# MotorDriver.net
KiCad netlist of a schematic drawn in EAGLE
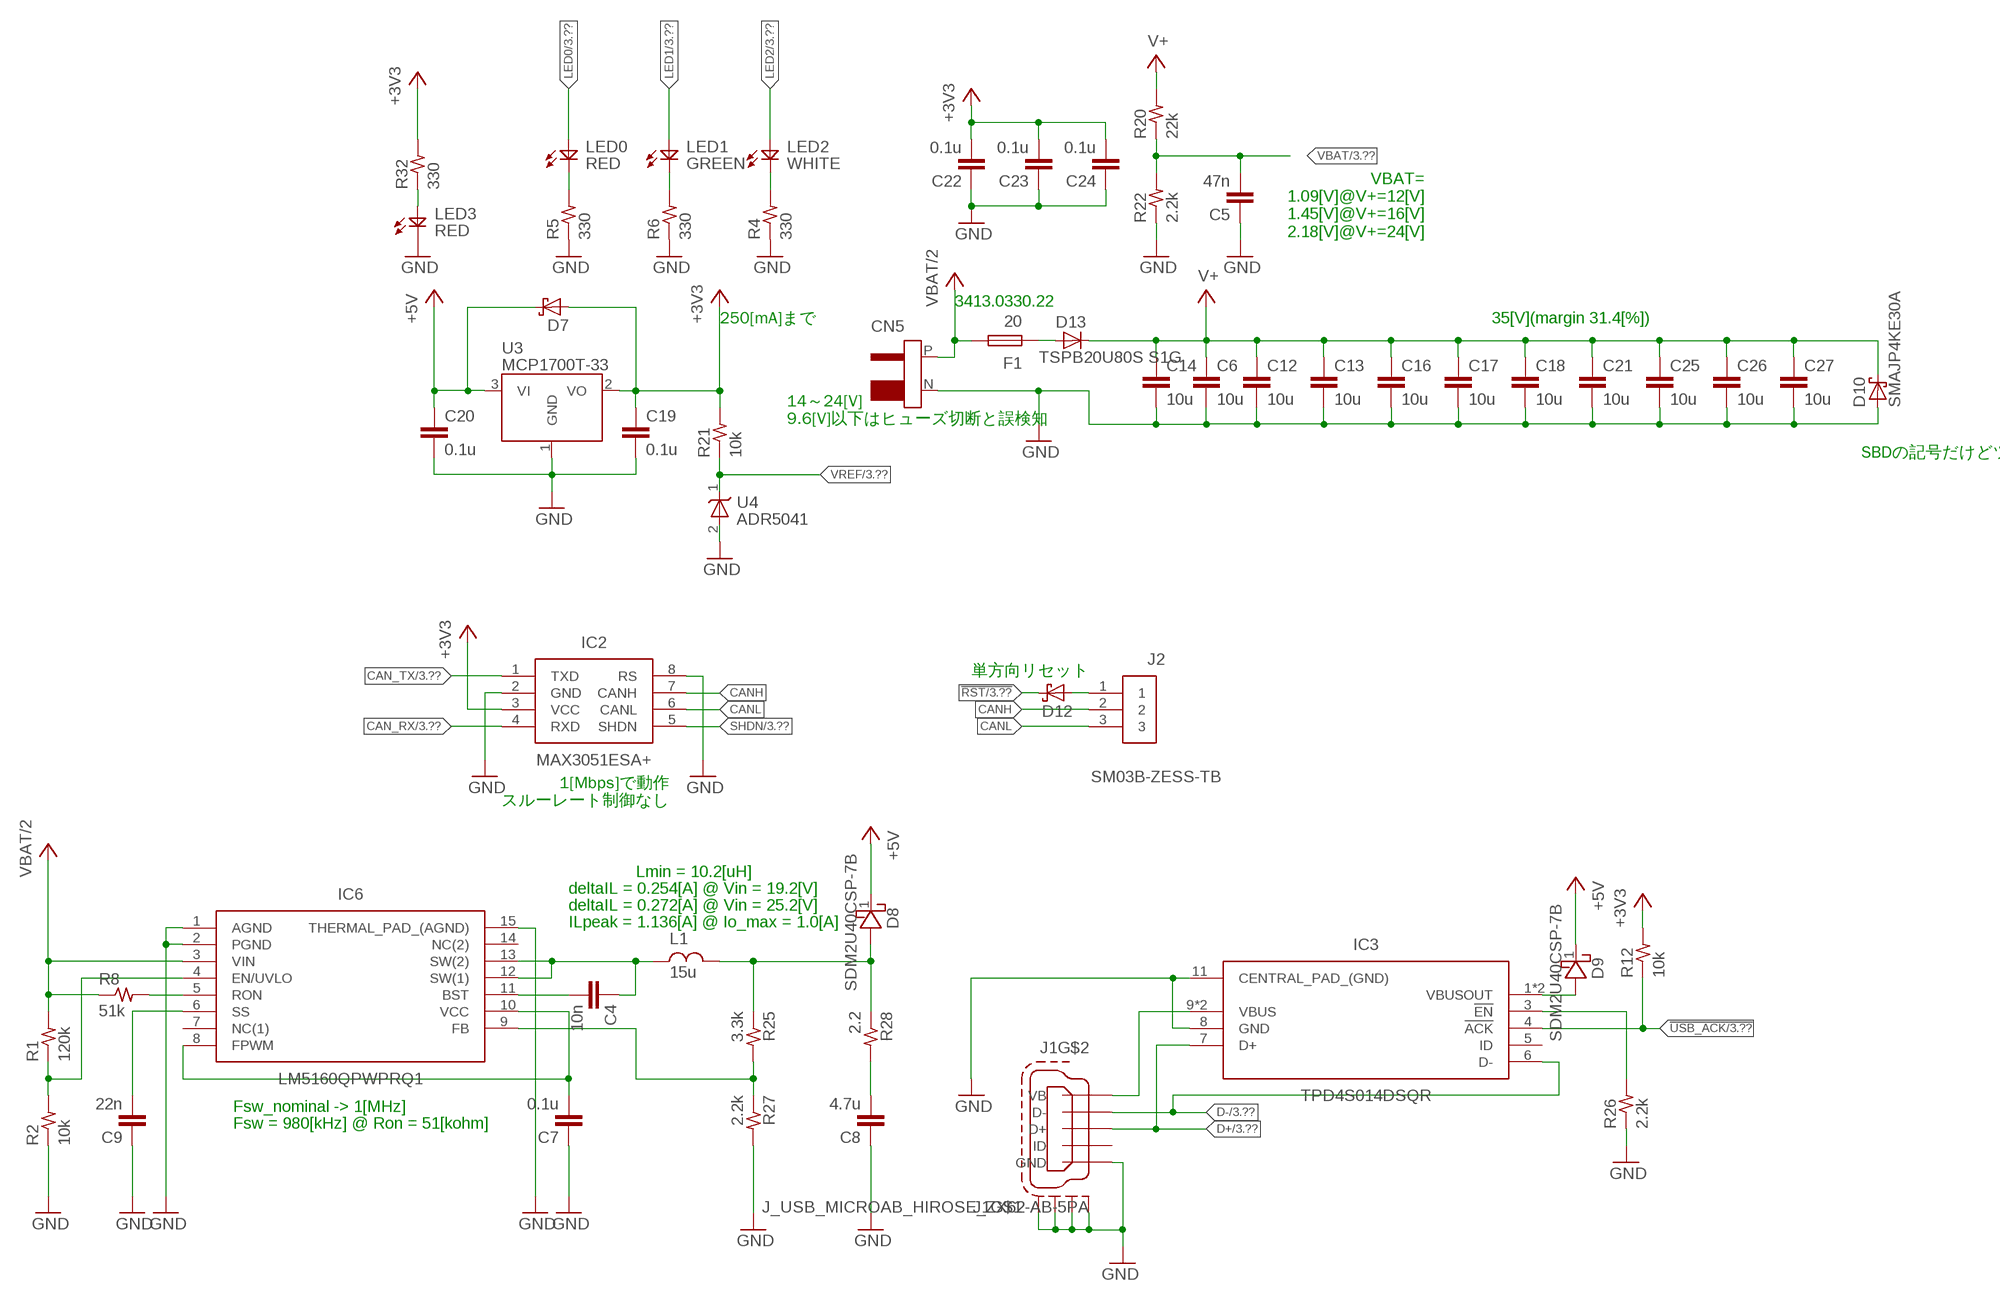
[diagram p0: schematic, sheet 1]
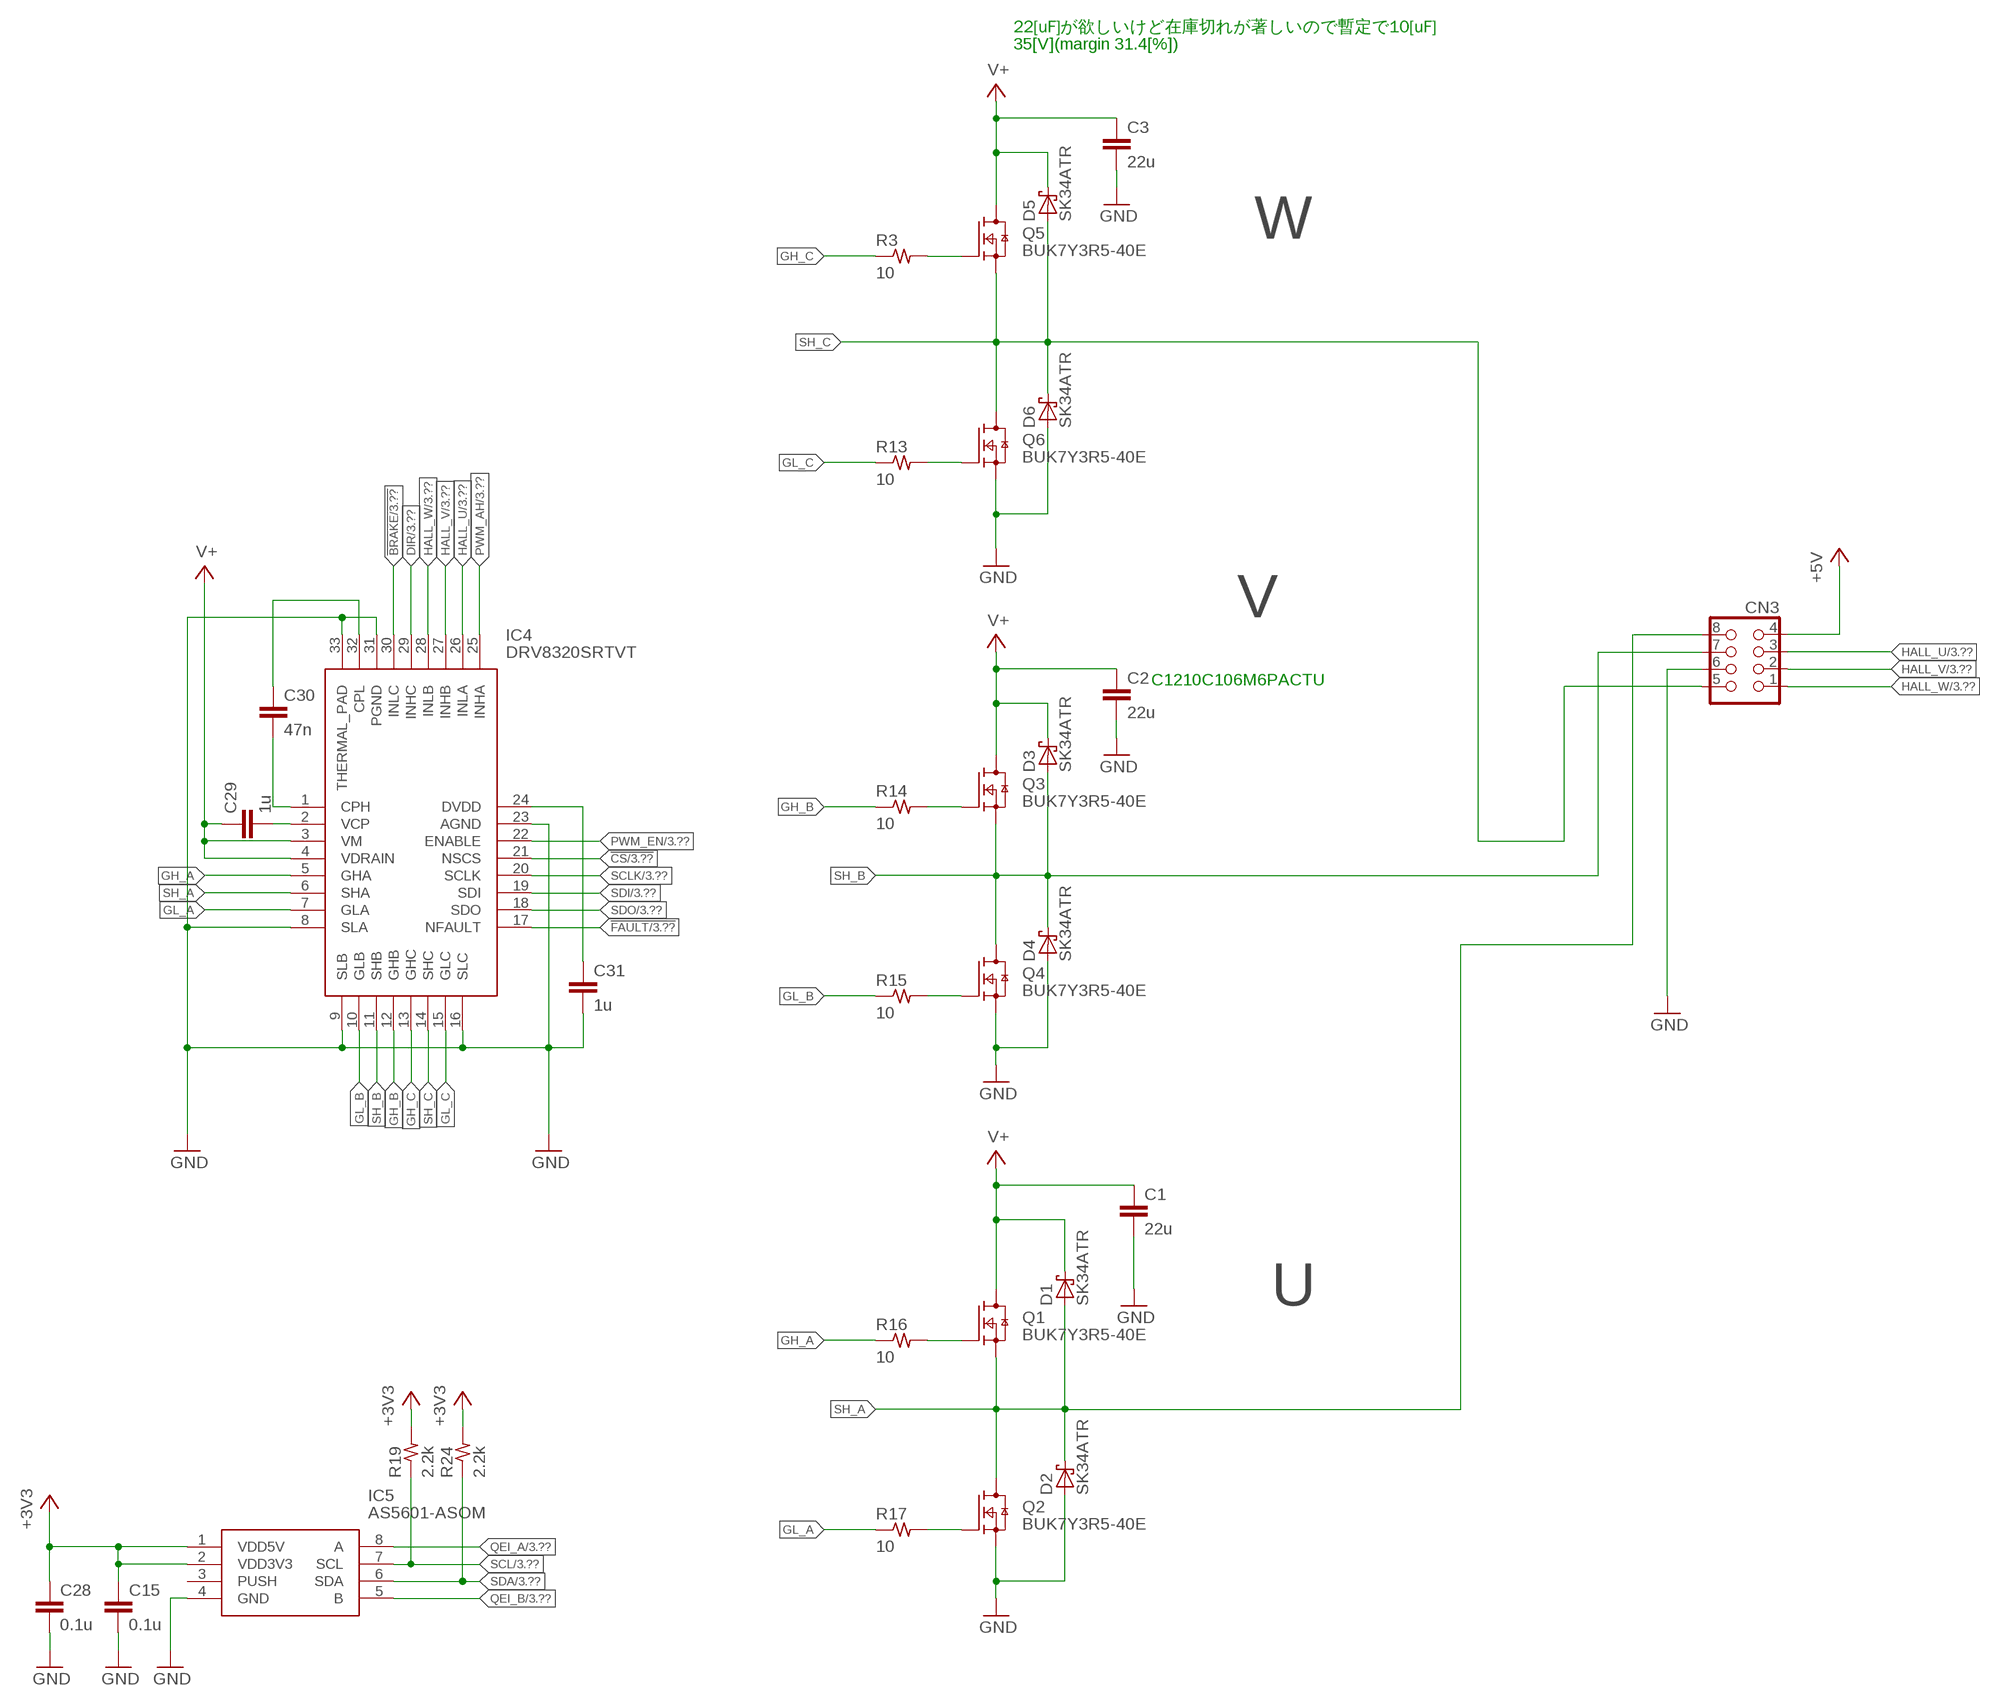
[diagram p1: schematic, sheet 2]
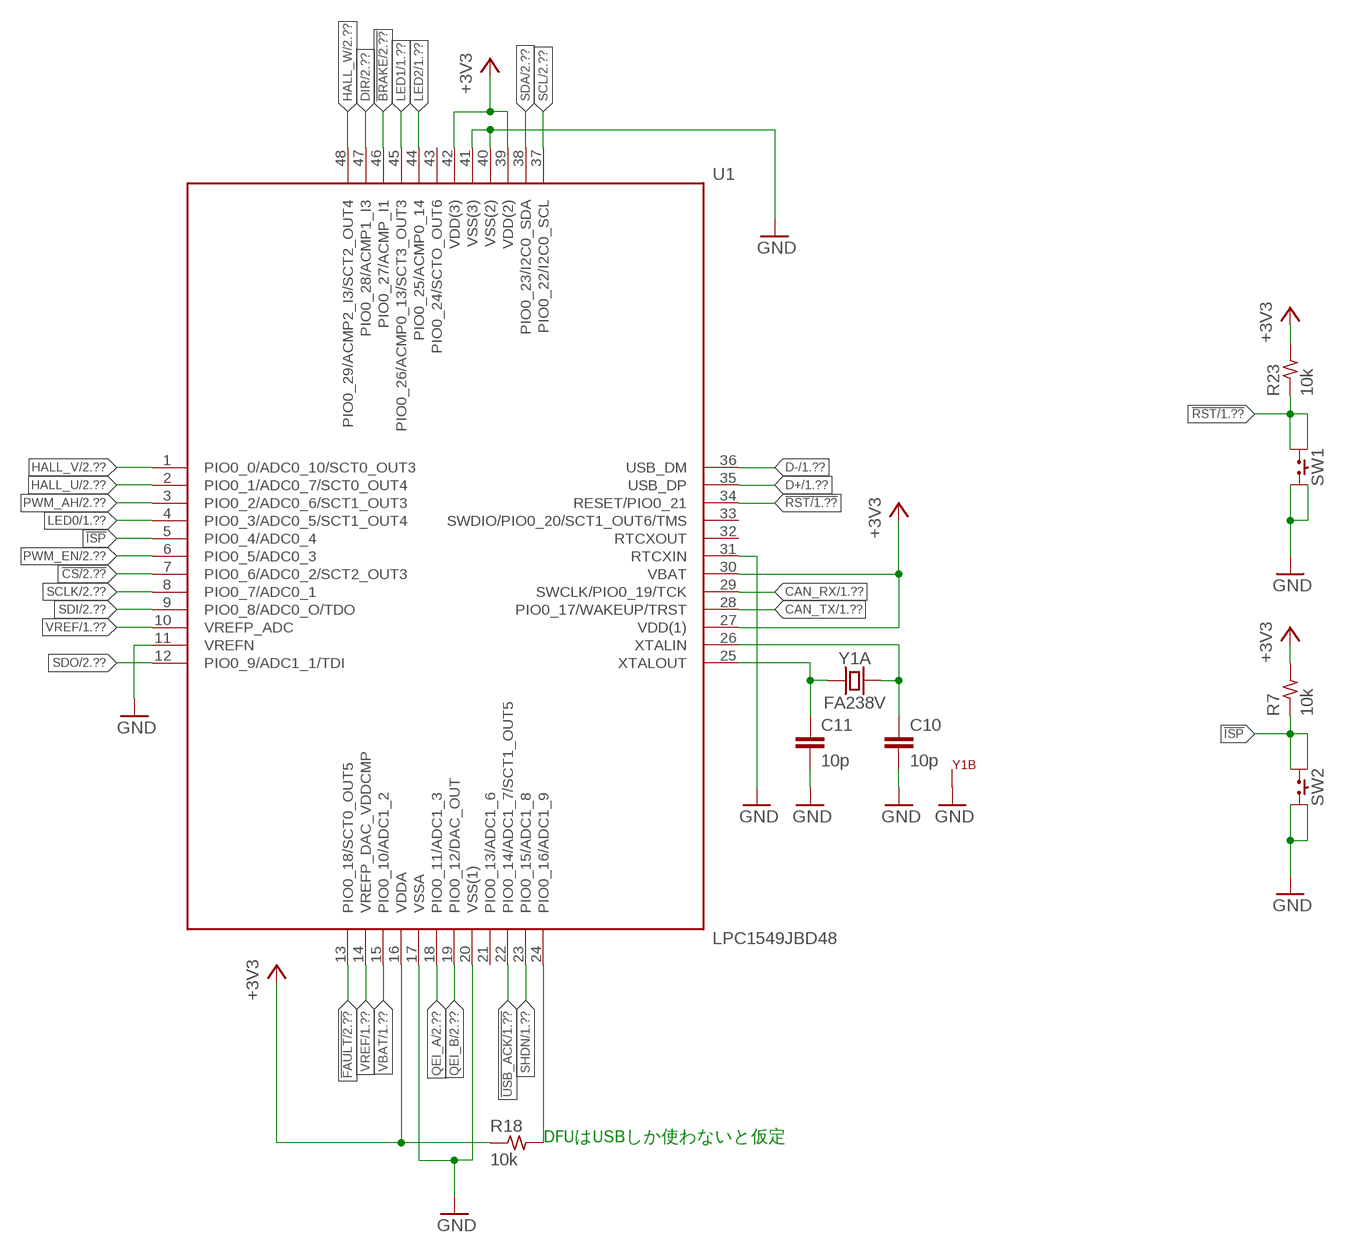
[diagram p2: schematic, sheet 3]

(export (version "E")
  (design (tool "Eeschema 10.0.6"))
  (components
    (comp (ref "C10")
      (value "10p")
      (footprint "eagle-import:C1005")
      (libsource (lib "eagle-import") (part "C1005"))
    )
    (comp (ref "C11")
      (value "10p")
      (footprint "eagle-import:C1005")
      (libsource (lib "eagle-import") (part "C1005"))
    )
    (comp (ref "R7")
      (value "10k")
      (footprint "eagle-import:R1005")
      (libsource (lib "eagle-import") (part "R1005"))
    )
    (comp (ref "R18")
      (value "10k")
      (footprint "eagle-import:R1005")
      (libsource (lib "eagle-import") (part "R1005"))
    )
    (comp (ref "R23")
      (value "10k")
      (footprint "eagle-import:R1005")
      (libsource (lib "eagle-import") (part "R1005"))
    )
    (comp (ref "SW1")
      (value "SKRP")
      (footprint "eagle-import:SKRP")
      (libsource (lib "eagle-import") (part "SKRP"))
    )
    (comp (ref "SW2")
      (value "SKRP")
      (footprint "eagle-import:SKRP")
      (libsource (lib "eagle-import") (part "SKRP"))
    )
    (comp (ref "U1")
      (value "LPC1549JBD48")
      (footprint "eagle-import:QFP48")
      (libsource (lib "eagle-import") (part "LPC1549JBD48"))
    )
    (comp (ref "Y1")
      (value "FA238V")
      (footprint "eagle-import:EPSON_FA238V")
      (libsource (lib "eagle-import") (part "FA238V"))
    )
    (comp (ref "C4")
      (value "10n")
      (footprint "eagle-import:C1005")
      (libsource (lib "eagle-import") (part "C1005"))
    )
    (comp (ref "C5")
      (value "47n")
      (footprint "eagle-import:C1005")
      (libsource (lib "eagle-import") (part "C1005"))
    )
    (comp (ref "C6")
      (value "10u")
      (footprint "eagle-import:C3225")
      (libsource (lib "eagle-import") (part "C3225"))
    )
    (comp (ref "C7")
      (value "0.1u")
      (footprint "eagle-import:C1005")
      (libsource (lib "eagle-import") (part "C1005"))
    )
    (comp (ref "C8")
      (value "4.7u")
      (footprint "eagle-import:1608")
      (libsource (lib "eagle-import") (part "Passive_1073310_C1608"))
    )
    (comp (ref "C9")
      (value "22n")
      (footprint "eagle-import:C1005")
      (libsource (lib "eagle-import") (part "C1005"))
    )
    (comp (ref "C12")
      (value "10u")
      (footprint "eagle-import:C3225")
      (libsource (lib "eagle-import") (part "C3225"))
    )
    (comp (ref "C13")
      (value "10u")
      (footprint "eagle-import:C3225")
      (libsource (lib "eagle-import") (part "C3225"))
    )
    (comp (ref "C14")
      (value "10u")
      (footprint "eagle-import:C3225")
      (libsource (lib "eagle-import") (part "C3225"))
    )
    (comp (ref "C16")
      (value "10u")
      (footprint "eagle-import:C3225")
      (libsource (lib "eagle-import") (part "C3225"))
    )
    (comp (ref "C17")
      (value "10u")
      (footprint "eagle-import:C3225")
      (libsource (lib "eagle-import") (part "C3225"))
    )
    (comp (ref "C18")
      (value "10u")
      (footprint "eagle-import:C3225")
      (libsource (lib "eagle-import") (part "C3225"))
    )
    (comp (ref "C19")
      (value "0.1u")
      (footprint "eagle-import:C1005")
      (libsource (lib "eagle-import") (part "C1005"))
    )
    (comp (ref "C20")
      (value "0.1u")
      (footprint "eagle-import:C1005")
      (libsource (lib "eagle-import") (part "C1005"))
    )
    (comp (ref "C21")
      (value "10u")
      (footprint "eagle-import:C3225")
      (libsource (lib "eagle-import") (part "C3225"))
    )
    (comp (ref "C22")
      (value "0.1u")
      (footprint "eagle-import:C1005")
      (libsource (lib "eagle-import") (part "C1005"))
    )
    (comp (ref "C23")
      (value "0.1u")
      (footprint "eagle-import:C1005")
      (libsource (lib "eagle-import") (part "C1005"))
    )
    (comp (ref "C24")
      (value "0.1u")
      (footprint "eagle-import:C1005")
      (libsource (lib "eagle-import") (part "C1005"))
    )
    (comp (ref "C25")
      (value "10u")
      (footprint "eagle-import:C3225")
      (libsource (lib "eagle-import") (part "C3225"))
    )
    (comp (ref "C26")
      (value "10u")
      (footprint "eagle-import:C3225")
      (libsource (lib "eagle-import") (part "C3225"))
    )
    (comp (ref "C27")
      (value "10u")
      (footprint "eagle-import:C3225")
      (libsource (lib "eagle-import") (part "C3225"))
    )
    (comp (ref "CN5")
      (value "T-CON")
      (footprint "eagle-import:T-CON")
      (libsource (lib "eagle-import") (part "T-CON"))
    )
    (comp (ref "D7")
      (value "SBD-SOD523")
      (footprint "eagle-import:DIODE_SOD523")
      (libsource (lib "eagle-import") (part "SBD-SOD523"))
    )
    (comp (ref "D8")
      (value "SDM2U40CSP-7B")
      (footprint "eagle-import:X3-WLB1608-2")
      (libsource (lib "eagle-import") (part "SDM2U40CSP-7B"))
    )
    (comp (ref "D9")
      (value "SDM2U40CSP-7B")
      (footprint "eagle-import:X3-WLB1608-2")
      (libsource (lib "eagle-import") (part "SDM2U40CSP-7B"))
    )
    (comp (ref "D10")
      (value "SMAJP4KE30A")
      (footprint "eagle-import:DO-214AC")
      (libsource (lib "eagle-import") (part "SBD-DO-214AC"))
    )
    (comp (ref "D12")
      (value "SBD-SOD523")
      (footprint "eagle-import:DIODE_SOD523")
      (libsource (lib "eagle-import") (part "SBD-SOD523"))
    )
    (comp (ref "D13")
      (value "TSPB20U80S S1G")
      (footprint "eagle-import:SMPC")
      (libsource (lib "eagle-import") (part "DIODE-SMPC"))
    )
    (comp (ref "F1")
      (value "20")
      (footprint "eagle-import:3216")
      (libsource (lib "eagle-import") (part "F3216"))
    )
    (comp (ref "IC2")
      (value "MAX3051ESA+")
      (footprint "eagle-import:SOIC127P600X175-8N")
      (fields (field (name "RS_PART_NUMBER") "7329005"))
      (libsource (lib "eagle-import") (part "MAX3051ESA+"))
    )
    (comp (ref "IC3")
      (value "TPD4S014DSQR")
      (footprint "eagle-import:SON40P200X200X80-11N")
      (fields (field (name "RS_PART_NUMBER") "7422968"))
      (libsource (lib "eagle-import") (part "TPD4S014DSQR"))
    )
    (comp (ref "IC6")
      (value "LM5160QPWPRQ1")
      (footprint "eagle-import:SOP65P640X110-15N")
      (libsource (lib "eagle-import") (part "LM5160QPWPRQ1"))
    )
    (comp (ref "J1")
      (value "J_USB_MICROAB_HIROSE_ZX62-AB-5PA")
      (footprint "eagle-import:J_USB_MICROAB_HIROSE_ZX62-AB-5PA")
      (libsource (lib "eagle-import") (part "J_USB_MICROAB_HIROSE_ZX62-AB-5PA"))
    )
    (comp (ref "J2")
      (value "SM03B-ZESS-TB")
      (footprint "eagle-import:SM03B-ZESS-TB")
      (libsource (lib "eagle-import") (part "SM03B-ZESS-TB"))
    )
    (comp (ref "L1")
      (value "15u")
      (footprint "eagle-import:L4949")
      (libsource (lib "eagle-import") (part "L50"))
    )
    (comp (ref "LED0")
      (value "RED")
      (footprint "eagle-import:LED1608")
      (libsource (lib "eagle-import") (part "LED1608"))
    )
    (comp (ref "LED1")
      (value "GREEN")
      (footprint "eagle-import:LED1608")
      (libsource (lib "eagle-import") (part "LED1608"))
    )
    (comp (ref "LED2")
      (value "WHITE")
      (footprint "eagle-import:LED1608")
      (libsource (lib "eagle-import") (part "LED1608"))
    )
    (comp (ref "LED3")
      (value "RED")
      (footprint "eagle-import:LED1608")
      (libsource (lib "eagle-import") (part "LED1608"))
    )
    (comp (ref "R1")
      (value "120k")
      (footprint "eagle-import:R1005")
      (libsource (lib "eagle-import") (part "R1005"))
    )
    (comp (ref "R2")
      (value "10k")
      (footprint "eagle-import:R1005")
      (libsource (lib "eagle-import") (part "R1005"))
    )
    (comp (ref "R4")
      (value "330")
      (footprint "eagle-import:R1005")
      (libsource (lib "eagle-import") (part "R1005"))
    )
    (comp (ref "R5")
      (value "330")
      (footprint "eagle-import:R1005")
      (libsource (lib "eagle-import") (part "R1005"))
    )
    (comp (ref "R6")
      (value "330")
      (footprint "eagle-import:R1005")
      (libsource (lib "eagle-import") (part "R1005"))
    )
    (comp (ref "R8")
      (value "51k")
      (footprint "eagle-import:R1005")
      (libsource (lib "eagle-import") (part "R1005"))
    )
    (comp (ref "R12")
      (value "10k")
      (footprint "eagle-import:R1005")
      (libsource (lib "eagle-import") (part "R1005"))
    )
    (comp (ref "R20")
      (value "22k")
      (footprint "eagle-import:R1005")
      (libsource (lib "eagle-import") (part "R1005"))
    )
    (comp (ref "R21")
      (value "10k")
      (footprint "eagle-import:R1005")
      (libsource (lib "eagle-import") (part "R1005"))
    )
    (comp (ref "R22")
      (value "2.2k")
      (footprint "eagle-import:R1005")
      (libsource (lib "eagle-import") (part "R1005"))
    )
    (comp (ref "R25")
      (value "3.3k")
      (footprint "eagle-import:R1005")
      (libsource (lib "eagle-import") (part "R1005"))
    )
    (comp (ref "R26")
      (value "2.2k")
      (footprint "eagle-import:R1005")
      (libsource (lib "eagle-import") (part "R1005"))
    )
    (comp (ref "R27")
      (value "2.2k")
      (footprint "eagle-import:R1005")
      (libsource (lib "eagle-import") (part "R1005"))
    )
    (comp (ref "R28")
      (value "2.2")
      (footprint "eagle-import:R1005")
      (libsource (lib "eagle-import") (part "R1005"))
    )
    (comp (ref "R32")
      (value "330")
      (footprint "eagle-import:R1005")
      (libsource (lib "eagle-import") (part "R1005"))
    )
    (comp (ref "U3")
      (value "MCP1700T-33")
      (footprint "eagle-import:SOT23-3")
      (libsource (lib "eagle-import") (part "MCP1700T-33"))
    )
    (comp (ref "U4")
      (value "ADR5041")
      (footprint "eagle-import:SC70-3")
      (libsource (lib "eagle-import") (part "ADR5041"))
    )
    (comp (ref "C1")
      (value "22u")
      (footprint "eagle-import:C3225")
      (libsource (lib "eagle-import") (part "C3225"))
    )
    (comp (ref "C2")
      (value "22u")
      (footprint "eagle-import:C3225")
      (libsource (lib "eagle-import") (part "C3225"))
    )
    (comp (ref "C3")
      (value "22u")
      (footprint "eagle-import:C3225")
      (libsource (lib "eagle-import") (part "C3225"))
    )
    (comp (ref "C15")
      (value "0.1u")
      (footprint "eagle-import:C1005")
      (libsource (lib "eagle-import") (part "C1005"))
    )
    (comp (ref "C28")
      (value "0.1u")
      (footprint "eagle-import:C1005")
      (libsource (lib "eagle-import") (part "C1005"))
    )
    (comp (ref "C29")
      (value "1u")
      (footprint "eagle-import:C1005")
      (libsource (lib "eagle-import") (part "C1005"))
    )
    (comp (ref "C30")
      (value "47n")
      (footprint "eagle-import:C1005")
      (libsource (lib "eagle-import") (part "C1005"))
    )
    (comp (ref "C31")
      (value "1u")
      (footprint "eagle-import:C1005")
      (libsource (lib "eagle-import") (part "C1005"))
    )
    (comp (ref "CN3")
      (value "43045-0800")
      (footprint "eagle-import:43045-0800")
      (libsource (lib "eagle-import") (part "43045-0800"))
    )
    (comp (ref "D1")
      (value "SK34ATR")
      (footprint "eagle-import:DO-214AC")
      (libsource (lib "eagle-import") (part "SBD-DO-214AC"))
    )
    (comp (ref "D2")
      (value "SK34ATR")
      (footprint "eagle-import:DO-214AC")
      (libsource (lib "eagle-import") (part "SBD-DO-214AC"))
    )
    (comp (ref "D3")
      (value "SK34ATR")
      (footprint "eagle-import:DO-214AC")
      (libsource (lib "eagle-import") (part "SBD-DO-214AC"))
    )
    (comp (ref "D4")
      (value "SK34ATR")
      (footprint "eagle-import:DO-214AC")
      (libsource (lib "eagle-import") (part "SBD-DO-214AC"))
    )
    (comp (ref "D5")
      (value "SK34ATR")
      (footprint "eagle-import:DO-214AC")
      (libsource (lib "eagle-import") (part "SBD-DO-214AC"))
    )
    (comp (ref "D6")
      (value "SK34ATR")
      (footprint "eagle-import:DO-214AC")
      (libsource (lib "eagle-import") (part "SBD-DO-214AC"))
    )
    (comp (ref "IC4")
      (value "DRV8320SRTVT")
      (footprint "eagle-import:QFN50P500X500X80-33N")
      (libsource (lib "eagle-import") (part "DRV8320SRTVT"))
    )
    (comp (ref "IC5")
      (value "AS5601-ASOM")
      (footprint "eagle-import:SOIC127P600X175-8N")
      (fields (field (name "RS_PART_NUMBER") "1700757"))
      (libsource (lib "eagle-import") (part "AS5601-ASOM"))
    )
    (comp (ref "Q1")
      (value "BUK7Y3R5-40E")
      (footprint "eagle-import:SOT669")
      (libsource (lib "eagle-import") (part "BUK7Y3R5-40E"))
    )
    (comp (ref "Q2")
      (value "BUK7Y3R5-40E")
      (footprint "eagle-import:SOT669")
      (libsource (lib "eagle-import") (part "BUK7Y3R5-40E"))
    )
    (comp (ref "Q3")
      (value "BUK7Y3R5-40E")
      (footprint "eagle-import:SOT669")
      (libsource (lib "eagle-import") (part "BUK7Y3R5-40E"))
    )
    (comp (ref "Q4")
      (value "BUK7Y3R5-40E")
      (footprint "eagle-import:SOT669")
      (libsource (lib "eagle-import") (part "BUK7Y3R5-40E"))
    )
    (comp (ref "Q5")
      (value "BUK7Y3R5-40E")
      (footprint "eagle-import:SOT669")
      (libsource (lib "eagle-import") (part "BUK7Y3R5-40E"))
    )
    (comp (ref "Q6")
      (value "BUK7Y3R5-40E")
      (footprint "eagle-import:SOT669")
      (libsource (lib "eagle-import") (part "BUK7Y3R5-40E"))
    )
    (comp (ref "R3")
      (value "10")
      (footprint "eagle-import:R1608")
      (libsource (lib "eagle-import") (part "R1608"))
    )
    (comp (ref "R13")
      (value "10")
      (footprint "eagle-import:R1608")
      (libsource (lib "eagle-import") (part "R1608"))
    )
    (comp (ref "R14")
      (value "10")
      (footprint "eagle-import:R1608")
      (libsource (lib "eagle-import") (part "R1608"))
    )
    (comp (ref "R15")
      (value "10")
      (footprint "eagle-import:R1608")
      (libsource (lib "eagle-import") (part "R1608"))
    )
    (comp (ref "R16")
      (value "10")
      (footprint "eagle-import:R1608")
      (libsource (lib "eagle-import") (part "R1608"))
    )
    (comp (ref "R17")
      (value "10")
      (footprint "eagle-import:R1608")
      (libsource (lib "eagle-import") (part "R1608"))
    )
    (comp (ref "R19")
      (value "2.2k")
      (footprint "eagle-import:R1005")
      (libsource (lib "eagle-import") (part "R1005"))
    )
    (comp (ref "R24")
      (value "2.2k")
      (footprint "eagle-import:R1005")
      (libsource (lib "eagle-import") (part "R1005"))
    )
  )
  (nets
    (net (code "1") (name "+3V3") (class "Default")
      (node (ref "C15") (pin "1") (pinfunction "1_1") (pintype "passive"))
      (node (ref "C19") (pin "1") (pinfunction "1_1") (pintype "passive"))
      (node (ref "C22") (pin "2") (pinfunction "2_2") (pintype "passive"))
      (node (ref "C23") (pin "2") (pinfunction "2_2") (pintype "passive"))
      (node (ref "C24") (pin "2") (pinfunction "2_2") (pintype "passive"))
      (node (ref "C28") (pin "1") (pinfunction "1_1") (pintype "passive"))
      (node (ref "D7") (pin "A") (pinfunction "A_A") (pintype "passive"))
      (node (ref "IC2") (pin "3") (pinfunction "VCC_3") (pintype "power_in"))
      (node (ref "IC5") (pin "1") (pinfunction "VDD5V_1") (pintype "power_in"))
      (node (ref "IC5") (pin "2") (pinfunction "VDD3V3_2") (pintype "power_in"))
      (node (ref "R12") (pin "2") (pinfunction "2_2") (pintype "passive"))
      (node (ref "R18") (pin "1") (pinfunction "1_1") (pintype "passive"))
      (node (ref "R19") (pin "2") (pinfunction "2_2") (pintype "passive"))
      (node (ref "R21") (pin "2") (pinfunction "2_2") (pintype "passive"))
      (node (ref "R23") (pin "2") (pinfunction "2_2") (pintype "passive"))
      (node (ref "R24") (pin "2") (pinfunction "2_2") (pintype "passive"))
      (node (ref "R32") (pin "2") (pinfunction "2_2") (pintype "passive"))
      (node (ref "R7") (pin "2") (pinfunction "2_2") (pintype "passive"))
      (node (ref "U1") (pin "16") (pinfunction "VDDA_16") (pintype "passive"))
      (node (ref "U1") (pin "27") (pinfunction "VDD(1)_27") (pintype "passive"))
      (node (ref "U1") (pin "30") (pinfunction "VBAT_30") (pintype "passive"))
      (node (ref "U1") (pin "39") (pinfunction "VDD(2)_39") (pintype "passive"))
      (node (ref "U1") (pin "42") (pinfunction "VDD(3)_42") (pintype "passive"))
      (node (ref "U3") (pin "2") (pinfunction "VO_2") (pintype "bidirectional"))
    )
    (net (code "2") (name "+5V") (class "Default")
      (node (ref "C20") (pin "1") (pinfunction "1_1") (pintype "passive"))
      (node (ref "CN3") (pin "4") (pinfunction "4_4") (pintype "passive"))
      (node (ref "D7") (pin "K") (pinfunction "K_K") (pintype "passive"))
      (node (ref "D8") (pin "1") (pinfunction "K_1") (pintype "passive"))
      (node (ref "D9") (pin "1") (pinfunction "K_1") (pintype "passive"))
      (node (ref "U3") (pin "3") (pinfunction "VI_3") (pintype "bidirectional"))
    )
    (net (code "3") (name "CANH") (class "Default")
      (node (ref "IC2") (pin "7") (pinfunction "CANH_7") (pintype "passive"))
      (node (ref "J2") (pin "2") (pinfunction "2_2") (pintype "passive"))
    )
    (net (code "4") (name "CANL") (class "Default")
      (node (ref "IC2") (pin "6") (pinfunction "CANL_6") (pintype "passive"))
      (node (ref "J2") (pin "3") (pinfunction "3_3") (pintype "passive"))
    )
    (net (code "5") (name "CAN_RX") (class "Default")
      (node (ref "IC2") (pin "4") (pinfunction "RXD_4") (pintype "output"))
      (node (ref "U1") (pin "29") (pinfunction "SWCLK/PIO0_19/TCK_29") (pintype "passive"))
    )
    (net (code "6") (name "CAN_TX") (class "Default")
      (node (ref "IC2") (pin "1") (pinfunction "TXD_1") (pintype "input"))
      (node (ref "U1") (pin "28") (pinfunction "PIO0_17/WAKEUP/TRST_28") (pintype "passive"))
    )
    (net (code "7") (name "D+") (class "Default")
      (node (ref "IC3") (pin "7") (pinfunction "D+_7") (pintype "passive"))
      (node (ref "J1") (pin "P$3") (pinfunction "D+_P$3") (pintype "passive"))
      (node (ref "U1") (pin "35") (pinfunction "USB_DP_35") (pintype "passive"))
    )
    (net (code "8") (name "D-") (class "Default")
      (node (ref "IC3") (pin "6") (pinfunction "D-_6") (pintype "passive"))
      (node (ref "J1") (pin "P$2") (pinfunction "D-_P$2") (pintype "passive"))
      (node (ref "U1") (pin "36") (pinfunction "USB_DM_36") (pintype "passive"))
    )
    (net (code "9") (name "DIR") (class "Default")
      (node (ref "IC4") (pin "29") (pinfunction "INHC_29") (pintype "bidirectional"))
      (node (ref "U1") (pin "47") (pinfunction "PIO0_28/ACMP1_I3_47") (pintype "passive"))
    )
    (net (code "10") (name "GH_A") (class "Default")
      (node (ref "IC4") (pin "5") (pinfunction "GHA_5") (pintype "bidirectional"))
      (node (ref "R16") (pin "1") (pinfunction "1_1") (pintype "passive"))
    )
    (net (code "11") (name "GH_B") (class "Default")
      (node (ref "IC4") (pin "12") (pinfunction "GHB_12") (pintype "bidirectional"))
      (node (ref "R14") (pin "1") (pinfunction "1_1") (pintype "passive"))
    )
    (net (code "12") (name "GH_C") (class "Default")
      (node (ref "IC4") (pin "13") (pinfunction "GHC_13") (pintype "bidirectional"))
      (node (ref "R3") (pin "1") (pinfunction "1_1") (pintype "passive"))
    )
    (net (code "13") (name "GL_A") (class "Default")
      (node (ref "IC4") (pin "7") (pinfunction "GLA_7") (pintype "bidirectional"))
      (node (ref "R17") (pin "1") (pinfunction "1_1") (pintype "passive"))
    )
    (net (code "14") (name "GL_B") (class "Default")
      (node (ref "IC4") (pin "10") (pinfunction "GLB_10") (pintype "bidirectional"))
      (node (ref "R15") (pin "1") (pinfunction "1_1") (pintype "passive"))
    )
    (net (code "15") (name "GL_C") (class "Default")
      (node (ref "IC4") (pin "15") (pinfunction "GLC_15") (pintype "bidirectional"))
      (node (ref "R13") (pin "1") (pinfunction "1_1") (pintype "passive"))
    )
    (net (code "16") (name "GND") (class "Default")
      (node (ref "C1") (pin "2") (pinfunction "2_2") (pintype "passive"))
      (node (ref "C10") (pin "2") (pinfunction "2_2") (pintype "passive"))
      (node (ref "C11") (pin "2") (pinfunction "2_2") (pintype "passive"))
      (node (ref "C12") (pin "2") (pinfunction "2_2") (pintype "passive"))
      (node (ref "C13") (pin "2") (pinfunction "2_2") (pintype "passive"))
      (node (ref "C14") (pin "2") (pinfunction "2_2") (pintype "passive"))
      (node (ref "C15") (pin "2") (pinfunction "2_2") (pintype "passive"))
      (node (ref "C16") (pin "2") (pinfunction "2_2") (pintype "passive"))
      (node (ref "C17") (pin "2") (pinfunction "2_2") (pintype "passive"))
      (node (ref "C18") (pin "2") (pinfunction "2_2") (pintype "passive"))
      (node (ref "C19") (pin "2") (pinfunction "2_2") (pintype "passive"))
      (node (ref "C2") (pin "2") (pinfunction "2_2") (pintype "passive"))
      (node (ref "C20") (pin "2") (pinfunction "2_2") (pintype "passive"))
      (node (ref "C21") (pin "2") (pinfunction "2_2") (pintype "passive"))
      (node (ref "C22") (pin "1") (pinfunction "1_1") (pintype "passive"))
      (node (ref "C23") (pin "1") (pinfunction "1_1") (pintype "passive"))
      (node (ref "C24") (pin "1") (pinfunction "1_1") (pintype "passive"))
      (node (ref "C25") (pin "2") (pinfunction "2_2") (pintype "passive"))
      (node (ref "C26") (pin "2") (pinfunction "2_2") (pintype "passive"))
      (node (ref "C27") (pin "2") (pinfunction "2_2") (pintype "passive"))
      (node (ref "C28") (pin "2") (pinfunction "2_2") (pintype "passive"))
      (node (ref "C3") (pin "2") (pinfunction "2_2") (pintype "passive"))
      (node (ref "C31") (pin "2") (pinfunction "2_2") (pintype "passive"))
      (node (ref "C5") (pin "1") (pinfunction "1_1") (pintype "passive"))
      (node (ref "C6") (pin "2") (pinfunction "2_2") (pintype "passive"))
      (node (ref "C7") (pin "1") (pinfunction "1_1") (pintype "passive"))
      (node (ref "C8") (pin "1") (pinfunction "1_1") (pintype "passive"))
      (node (ref "C9") (pin "1") (pinfunction "1_1") (pintype "passive"))
      (node (ref "CN3") (pin "6") (pinfunction "6_6") (pintype "passive"))
      (node (ref "CN5") (pin "N") (pinfunction "N_N") (pintype "passive"))
      (node (ref "D10") (pin "A") (pinfunction "A_A") (pintype "passive"))
      (node (ref "D2") (pin "A") (pinfunction "A_A") (pintype "passive"))
      (node (ref "D4") (pin "A") (pinfunction "A_A") (pintype "passive"))
      (node (ref "D6") (pin "A") (pinfunction "A_A") (pintype "passive"))
      (node (ref "IC2") (pin "2") (pinfunction "GND_2") (pintype "power_in"))
      (node (ref "IC2") (pin "8") (pinfunction "RS_8") (pintype "input"))
      (node (ref "IC3") (pin "11") (pinfunction "CENTRAL_PAD_(GND)_11") (pintype "passive"))
      (node (ref "IC3") (pin "8") (pinfunction "GND_8") (pintype "passive"))
      (node (ref "IC4") (pin "16") (pinfunction "SLC_16") (pintype "bidirectional"))
      (node (ref "IC4") (pin "23") (pinfunction "AGND_23") (pintype "bidirectional"))
      (node (ref "IC4") (pin "31") (pinfunction "PGND_31") (pintype "bidirectional"))
      (node (ref "IC4") (pin "33") (pinfunction "THERMAL_PAD_33") (pintype "bidirectional"))
      (node (ref "IC4") (pin "8") (pinfunction "SLA_8") (pintype "bidirectional"))
      (node (ref "IC4") (pin "9") (pinfunction "SLB_9") (pintype "bidirectional"))
      (node (ref "IC5") (pin "4") (pinfunction "GND_4") (pintype "power_in"))
      (node (ref "IC6") (pin "1") (pinfunction "AGND_1") (pintype "passive"))
      (node (ref "IC6") (pin "15") (pinfunction "THERMAL_PAD_(AGND)_15") (pintype "passive"))
      (node (ref "IC6") (pin "2") (pinfunction "PGND_2") (pintype "passive"))
      (node (ref "J1") (pin "P$5") (pinfunction "GND_P$5") (pintype "passive"))
      (node (ref "J1") (pin "SHIELD1") (pinfunction "S1_SHIELD1") (pintype "passive"))
      (node (ref "J1") (pin "SHIELD2") (pinfunction "S2_SHIELD2") (pintype "passive"))
      (node (ref "J1") (pin "SHIELD3") (pinfunction "S3_SHIELD3") (pintype "passive"))
      (node (ref "J1") (pin "SHIELD4") (pinfunction "S4_SHIELD4") (pintype "passive"))
      (node (ref "LED3") (pin "K") (pinfunction "K_K") (pintype "passive"))
      (node (ref "Q2") (pin "1") (pinfunction "S_1") (pintype "passive"))
      (node (ref "Q2") (pin "2") (pinfunction "S_2") (pintype "passive"))
      (node (ref "Q2") (pin "3") (pinfunction "S_3") (pintype "passive"))
      (node (ref "Q4") (pin "1") (pinfunction "S_1") (pintype "passive"))
      (node (ref "Q4") (pin "2") (pinfunction "S_2") (pintype "passive"))
      (node (ref "Q4") (pin "3") (pinfunction "S_3") (pintype "passive"))
      (node (ref "Q6") (pin "1") (pinfunction "S_1") (pintype "passive"))
      (node (ref "Q6") (pin "2") (pinfunction "S_2") (pintype "passive"))
      (node (ref "Q6") (pin "3") (pinfunction "S_3") (pintype "passive"))
      (node (ref "R2") (pin "1") (pinfunction "1_1") (pintype "passive"))
      (node (ref "R22") (pin "1") (pinfunction "1_1") (pintype "passive"))
      (node (ref "R26") (pin "1") (pinfunction "1_1") (pintype "passive"))
      (node (ref "R27") (pin "2") (pinfunction "2_2") (pintype "passive"))
      (node (ref "R4") (pin "1") (pinfunction "1_1") (pintype "passive"))
      (node (ref "R5") (pin "1") (pinfunction "1_1") (pintype "passive"))
      (node (ref "R6") (pin "1") (pinfunction "1_1") (pintype "passive"))
      (node (ref "SW1") (pin "B1") (pinfunction "B1_B1") (pintype "passive"))
      (node (ref "SW1") (pin "B2") (pinfunction "B2_B2") (pintype "passive"))
      (node (ref "SW2") (pin "B1") (pinfunction "B1_B1") (pintype "passive"))
      (node (ref "SW2") (pin "B2") (pinfunction "B2_B2") (pintype "passive"))
      (node (ref "U1") (pin "11") (pinfunction "VREFN_11") (pintype "passive"))
      (node (ref "U1") (pin "17") (pinfunction "VSSA_17") (pintype "passive"))
      (node (ref "U1") (pin "20") (pinfunction "VSS(1)_20") (pintype "passive"))
      (node (ref "U1") (pin "31") (pinfunction "RTCXIN_31") (pintype "passive"))
      (node (ref "U1") (pin "40") (pinfunction "VSS(2)_40") (pintype "passive"))
      (node (ref "U1") (pin "41") (pinfunction "VSS(3)_41") (pintype "passive"))
      (node (ref "U3") (pin "1") (pinfunction "GND_1") (pintype "bidirectional"))
      (node (ref "U4") (pin "2") (pinfunction "A_2") (pintype "passive"))
      (node (ref "Y1") (pin "2") (pinfunction "1_2") (pintype "bidirectional"))
      (node (ref "Y1") (pin "4") (pinfunction "1_4") (pintype "bidirectional"))
    )
    (net (code "17") (name "HALL_U") (class "Default")
      (node (ref "CN3") (pin "3") (pinfunction "3_3") (pintype "passive"))
      (node (ref "IC4") (pin "26") (pinfunction "INLA_26") (pintype "bidirectional"))
      (node (ref "U1") (pin "2") (pinfunction "PIO0_1/ADC0_7/SCT0_OUT4_2") (pintype "passive"))
    )
    (net (code "18") (name "HALL_V") (class "Default")
      (node (ref "CN3") (pin "2") (pinfunction "2_2") (pintype "passive"))
      (node (ref "IC4") (pin "27") (pinfunction "INHB_27") (pintype "bidirectional"))
      (node (ref "U1") (pin "1") (pinfunction "PIO0_0/ADC0_10/SCT0_OUT3_1") (pintype "passive"))
    )
    (net (code "19") (name "HALL_W") (class "Default")
      (node (ref "CN3") (pin "1") (pinfunction "1_1") (pintype "passive"))
      (node (ref "IC4") (pin "28") (pinfunction "INLB_28") (pintype "bidirectional"))
      (node (ref "U1") (pin "48") (pinfunction "PIO0_29/ACMP2_I3/SCT2_OUT4_48") (pintype "passive"))
    )
    (net (code "20") (name "LED0") (class "Default")
      (node (ref "LED0") (pin "A") (pinfunction "A_A") (pintype "passive"))
      (node (ref "U1") (pin "4") (pinfunction "PIO0_3/ADC0_5/SCT1_OUT4_4") (pintype "passive"))
    )
    (net (code "21") (name "LED1") (class "Default")
      (node (ref "LED1") (pin "A") (pinfunction "A_A") (pintype "passive"))
      (node (ref "U1") (pin "45") (pinfunction "PIO0_26/ACMP0_13/SCT3_OUT3_45") (pintype "passive"))
    )
    (net (code "22") (name "LED2") (class "Default")
      (node (ref "LED2") (pin "A") (pinfunction "A_A") (pintype "passive"))
      (node (ref "U1") (pin "44") (pinfunction "PIO0_25/ACMP0_14_44") (pintype "passive"))
    )
    (net (code "23") (name "Net-(C8-Pad2)") (class "Default")
      (node (ref "C8") (pin "2") (pinfunction "2_2") (pintype "passive"))
      (node (ref "R28") (pin "2") (pinfunction "2_2") (pintype "passive"))
    )
    (net (code "24") (name "Net-(D8-A)") (class "Default")
      (node (ref "D8") (pin "2") (pinfunction "A_2") (pintype "passive"))
      (node (ref "L1") (pin "2") (pinfunction "2_2") (pintype "passive"))
      (node (ref "R25") (pin "1") (pinfunction "1_1") (pintype "passive"))
      (node (ref "R28") (pin "1") (pinfunction "1_1") (pintype "passive"))
    )
    (net (code "25") (name "Net-(D9-A)") (class "Default")
      (node (ref "D9") (pin "2") (pinfunction "A_2") (pintype "passive"))
      (node (ref "IC3") (pin "1") (pinfunction "VBUSOUT_1") (pintype "passive"))
      (node (ref "IC3") (pin "2") (pinfunction "VBUSOUT_2") (pintype "passive"))
    )
    (net (code "26") (name "Net-(D12-PadA)") (class "Default")
      (node (ref "D12") (pin "A") (pinfunction "A_A") (pintype "passive"))
      (node (ref "J2") (pin "1") (pinfunction "1_1") (pintype "passive"))
    )
    (net (code "27") (name "Net-(D13-A-Pad1)") (class "Default")
      (node (ref "D13") (pin "1") (pinfunction "A_1") (pintype "passive"))
      (node (ref "D13") (pin "2") (pinfunction "A_2") (pintype "passive"))
      (node (ref "F1") (pin "1") (pinfunction "1_1") (pintype "passive"))
    )
    (net (code "28") (name "Net-(IC3-~{EN})") (class "Default")
      (node (ref "IC3") (pin "3") (pinfunction "~{EN}_3") (pintype "passive"))
      (node (ref "R26") (pin "2") (pinfunction "2_2") (pintype "passive"))
    )
    (net (code "29") (name "Net-(IC4-CPH)") (class "Default")
      (node (ref "C30") (pin "2") (pinfunction "2_2") (pintype "passive"))
      (node (ref "IC4") (pin "1") (pinfunction "CPH_1") (pintype "bidirectional"))
    )
    (net (code "30") (name "Net-(IC4-CPL)") (class "Default")
      (node (ref "C30") (pin "1") (pinfunction "1_1") (pintype "passive"))
      (node (ref "IC4") (pin "32") (pinfunction "CPL_32") (pintype "bidirectional"))
    )
    (net (code "31") (name "Net-(IC4-DVDD)") (class "Default")
      (node (ref "C31") (pin "1") (pinfunction "1_1") (pintype "passive"))
      (node (ref "IC4") (pin "24") (pinfunction "DVDD_24") (pintype "bidirectional"))
    )
    (net (code "32") (name "Net-(IC4-VCP)") (class "Default")
      (node (ref "C29") (pin "2") (pinfunction "2_2") (pintype "passive"))
      (node (ref "IC4") (pin "2") (pinfunction "VCP_2") (pintype "bidirectional"))
    )
    (net (code "33") (name "Net-(IC6-BST)") (class "Default")
      (node (ref "C4") (pin "2") (pinfunction "2_2") (pintype "passive"))
      (node (ref "IC6") (pin "11") (pinfunction "BST_11") (pintype "passive"))
    )
    (net (code "34") (name "Net-(IC6-EN{slash}UVLO)") (class "Default")
      (node (ref "IC6") (pin "4") (pinfunction "EN/UVLO_4") (pintype "passive"))
      (node (ref "R1") (pin "1") (pinfunction "1_1") (pintype "passive"))
      (node (ref "R2") (pin "2") (pinfunction "2_2") (pintype "passive"))
    )
    (net (code "35") (name "Net-(IC6-FB)") (class "Default")
      (node (ref "IC6") (pin "9") (pinfunction "FB_9") (pintype "passive"))
      (node (ref "R25") (pin "2") (pinfunction "2_2") (pintype "passive"))
      (node (ref "R27") (pin "1") (pinfunction "1_1") (pintype "passive"))
    )
    (net (code "36") (name "Net-(IC6-FPWM)") (class "Default")
      (node (ref "C7") (pin "2") (pinfunction "2_2") (pintype "passive"))
      (node (ref "IC6") (pin "10") (pinfunction "VCC_10") (pintype "passive"))
      (node (ref "IC6") (pin "8") (pinfunction "FPWM_8") (pintype "passive"))
    )
    (net (code "37") (name "Net-(IC6-RON)") (class "Default")
      (node (ref "IC6") (pin "5") (pinfunction "RON_5") (pintype "passive"))
      (node (ref "R8") (pin "2") (pinfunction "2_2") (pintype "passive"))
    )
    (net (code "38") (name "Net-(IC6-SS)") (class "Default")
      (node (ref "C9") (pin "2") (pinfunction "2_2") (pintype "passive"))
      (node (ref "IC6") (pin "6") (pinfunction "SS_6") (pintype "passive"))
    )
    (net (code "39") (name "Net-(IC6-SW(1))") (class "Default")
      (node (ref "C4") (pin "1") (pinfunction "1_1") (pintype "passive"))
      (node (ref "IC6") (pin "12") (pinfunction "SW(1)_12") (pintype "passive"))
      (node (ref "IC6") (pin "13") (pinfunction "SW(2)_13") (pintype "passive"))
      (node (ref "L1") (pin "1") (pinfunction "1_1") (pintype "passive"))
    )
    (net (code "40") (name "Net-(J1B-VB)") (class "Default")
      (node (ref "IC3") (pin "10") (pinfunction "VBUS_10") (pintype "passive"))
      (node (ref "IC3") (pin "9") (pinfunction "VBUS_9") (pintype "passive"))
      (node (ref "J1") (pin "P$1") (pinfunction "VB_P$1") (pintype "passive"))
    )
    (net (code "41") (name "Net-(LED0-PadK)") (class "Default")
      (node (ref "LED0") (pin "K") (pinfunction "K_K") (pintype "passive"))
      (node (ref "R5") (pin "2") (pinfunction "2_2") (pintype "passive"))
    )
    (net (code "42") (name "Net-(LED1-PadK)") (class "Default")
      (node (ref "LED1") (pin "K") (pinfunction "K_K") (pintype "passive"))
      (node (ref "R6") (pin "2") (pinfunction "2_2") (pintype "passive"))
    )
    (net (code "43") (name "Net-(LED2-PadK)") (class "Default")
      (node (ref "LED2") (pin "K") (pinfunction "K_K") (pintype "passive"))
      (node (ref "R4") (pin "2") (pinfunction "2_2") (pintype "passive"))
    )
    (net (code "44") (name "Net-(LED3-PadA)") (class "Default")
      (node (ref "LED3") (pin "A") (pinfunction "A_A") (pintype "passive"))
      (node (ref "R32") (pin "1") (pinfunction "1_1") (pintype "passive"))
    )
    (net (code "45") (name "Net-(Q1-G)") (class "Default")
      (node (ref "Q1") (pin "4") (pinfunction "G_4") (pintype "passive"))
      (node (ref "R16") (pin "2") (pinfunction "2_2") (pintype "passive"))
    )
    (net (code "46") (name "Net-(Q2-G)") (class "Default")
      (node (ref "Q2") (pin "4") (pinfunction "G_4") (pintype "passive"))
      (node (ref "R17") (pin "2") (pinfunction "2_2") (pintype "passive"))
    )
    (net (code "47") (name "Net-(Q3-G)") (class "Default")
      (node (ref "Q3") (pin "4") (pinfunction "G_4") (pintype "passive"))
      (node (ref "R14") (pin "2") (pinfunction "2_2") (pintype "passive"))
    )
    (net (code "48") (name "Net-(Q4-G)") (class "Default")
      (node (ref "Q4") (pin "4") (pinfunction "G_4") (pintype "passive"))
      (node (ref "R15") (pin "2") (pinfunction "2_2") (pintype "passive"))
    )
    (net (code "49") (name "Net-(Q5-G)") (class "Default")
      (node (ref "Q5") (pin "4") (pinfunction "G_4") (pintype "passive"))
      (node (ref "R3") (pin "2") (pinfunction "2_2") (pintype "passive"))
    )
    (net (code "50") (name "Net-(Q6-G)") (class "Default")
      (node (ref "Q6") (pin "4") (pinfunction "G_4") (pintype "passive"))
      (node (ref "R13") (pin "2") (pinfunction "2_2") (pintype "passive"))
    )
    (net (code "51") (name "Net-(U1-PIO0_16{slash}ADC1_9)") (class "Default")
      (node (ref "R18") (pin "2") (pinfunction "2_2") (pintype "passive"))
      (node (ref "U1") (pin "24") (pinfunction "PIO0_16/ADC1_9_24") (pintype "passive"))
    )
    (net (code "52") (name "Net-(U1-XTALIN)") (class "Default")
      (node (ref "C10") (pin "1") (pinfunction "1_1") (pintype "passive"))
      (node (ref "U1") (pin "26") (pinfunction "XTALIN_26") (pintype "passive"))
      (node (ref "Y1") (pin "3") (pinfunction "3_3") (pintype "passive"))
    )
    (net (code "53") (name "Net-(U1-XTALOUT)") (class "Default")
      (node (ref "C11") (pin "1") (pinfunction "1_1") (pintype "passive"))
      (node (ref "U1") (pin "25") (pinfunction "XTALOUT_25") (pintype "passive"))
      (node (ref "Y1") (pin "1") (pinfunction "1_1") (pintype "passive"))
    )
    (net (code "54") (name "PWM_AH") (class "Default")
      (node (ref "IC4") (pin "25") (pinfunction "INHA_25") (pintype "bidirectional"))
      (node (ref "U1") (pin "3") (pinfunction "PIO0_2/ADC0_6/SCT1_OUT3_3") (pintype "passive"))
    )
    (net (code "55") (name "PWM_EN") (class "Default")
      (node (ref "IC4") (pin "22") (pinfunction "ENABLE_22") (pintype "bidirectional"))
      (node (ref "U1") (pin "6") (pinfunction "PIO0_5/ADC0_3_6") (pintype "passive"))
    )
    (net (code "56") (name "QEI_A") (class "Default")
      (node (ref "IC5") (pin "8") (pinfunction "A_8") (pintype "bidirectional"))
      (node (ref "U1") (pin "18") (pinfunction "PIO0_11/ADC1_3_18") (pintype "passive"))
    )
    (net (code "57") (name "QEI_B") (class "Default")
      (node (ref "IC5") (pin "5") (pinfunction "B_5") (pintype "bidirectional"))
      (node (ref "U1") (pin "19") (pinfunction "PIO0_12/DAC_OUT_19") (pintype "passive"))
    )
    (net (code "58") (name "SCL") (class "Default")
      (node (ref "IC5") (pin "7") (pinfunction "SCL_7") (pintype "bidirectional"))
      (node (ref "R19") (pin "1") (pinfunction "1_1") (pintype "passive"))
      (node (ref "U1") (pin "37") (pinfunction "PIO0_22/I2C0_SCL_37") (pintype "passive"))
    )
    (net (code "59") (name "SCLK") (class "Default")
      (node (ref "IC4") (pin "20") (pinfunction "SCLK_20") (pintype "bidirectional"))
      (node (ref "U1") (pin "8") (pinfunction "PIO0_7/ADC0_1_8") (pintype "passive"))
    )
    (net (code "60") (name "SDA") (class "Default")
      (node (ref "IC5") (pin "6") (pinfunction "SDA_6") (pintype "bidirectional"))
      (node (ref "R24") (pin "1") (pinfunction "1_1") (pintype "passive"))
      (node (ref "U1") (pin "38") (pinfunction "PIO0_23/I2C0_SDA_38") (pintype "passive"))
    )
    (net (code "61") (name "SDI") (class "Default")
      (node (ref "IC4") (pin "19") (pinfunction "SDI_19") (pintype "bidirectional"))
      (node (ref "U1") (pin "9") (pinfunction "PIO0_8/ADC0_O/TDO_9") (pintype "passive"))
    )
    (net (code "62") (name "SDO") (class "Default")
      (node (ref "IC4") (pin "18") (pinfunction "SDO_18") (pintype "bidirectional"))
      (node (ref "U1") (pin "12") (pinfunction "PIO0_9/ADC1_1/TDI_12") (pintype "passive"))
    )
    (net (code "63") (name "SHDN") (class "Default")
      (node (ref "IC2") (pin "5") (pinfunction "SHDN_5") (pintype "input"))
      (node (ref "U1") (pin "23") (pinfunction "PIO0_15/ADC1_8_23") (pintype "passive"))
    )
    (net (code "64") (name "SH_A") (class "Default")
      (node (ref "CN3") (pin "8") (pinfunction "8_8") (pintype "passive"))
      (node (ref "D1") (pin "A") (pinfunction "A_A") (pintype "passive"))
      (node (ref "D2") (pin "K") (pinfunction "K_K") (pintype "passive"))
      (node (ref "IC4") (pin "6") (pinfunction "SHA_6") (pintype "bidirectional"))
      (node (ref "Q1") (pin "1") (pinfunction "S_1") (pintype "passive"))
      (node (ref "Q1") (pin "2") (pinfunction "S_2") (pintype "passive"))
      (node (ref "Q1") (pin "3") (pinfunction "S_3") (pintype "passive"))
      (node (ref "Q2") (pin "MB") (pinfunction "D_MB") (pintype "passive"))
    )
    (net (code "65") (name "SH_B") (class "Default")
      (node (ref "CN3") (pin "7") (pinfunction "7_7") (pintype "passive"))
      (node (ref "D3") (pin "A") (pinfunction "A_A") (pintype "passive"))
      (node (ref "D4") (pin "K") (pinfunction "K_K") (pintype "passive"))
      (node (ref "IC4") (pin "11") (pinfunction "SHB_11") (pintype "bidirectional"))
      (node (ref "Q3") (pin "1") (pinfunction "S_1") (pintype "passive"))
      (node (ref "Q3") (pin "2") (pinfunction "S_2") (pintype "passive"))
      (node (ref "Q3") (pin "3") (pinfunction "S_3") (pintype "passive"))
      (node (ref "Q4") (pin "MB") (pinfunction "D_MB") (pintype "passive"))
    )
    (net (code "66") (name "SH_C") (class "Default")
      (node (ref "CN3") (pin "5") (pinfunction "5_5") (pintype "passive"))
      (node (ref "D5") (pin "A") (pinfunction "A_A") (pintype "passive"))
      (node (ref "D6") (pin "K") (pinfunction "K_K") (pintype "passive"))
      (node (ref "IC4") (pin "14") (pinfunction "SHC_14") (pintype "bidirectional"))
      (node (ref "Q5") (pin "1") (pinfunction "S_1") (pintype "passive"))
      (node (ref "Q5") (pin "2") (pinfunction "S_2") (pintype "passive"))
      (node (ref "Q5") (pin "3") (pinfunction "S_3") (pintype "passive"))
      (node (ref "Q6") (pin "MB") (pinfunction "D_MB") (pintype "passive"))
    )
    (net (code "67") (name "V+") (class "Default")
      (node (ref "C1") (pin "1") (pinfunction "1_1") (pintype "passive"))
      (node (ref "C12") (pin "1") (pinfunction "1_1") (pintype "passive"))
      (node (ref "C13") (pin "1") (pinfunction "1_1") (pintype "passive"))
      (node (ref "C14") (pin "1") (pinfunction "1_1") (pintype "passive"))
      (node (ref "C16") (pin "1") (pinfunction "1_1") (pintype "passive"))
      (node (ref "C17") (pin "1") (pinfunction "1_1") (pintype "passive"))
      (node (ref "C18") (pin "1") (pinfunction "1_1") (pintype "passive"))
      (node (ref "C2") (pin "1") (pinfunction "1_1") (pintype "passive"))
      (node (ref "C21") (pin "1") (pinfunction "1_1") (pintype "passive"))
      (node (ref "C25") (pin "1") (pinfunction "1_1") (pintype "passive"))
      (node (ref "C26") (pin "1") (pinfunction "1_1") (pintype "passive"))
      (node (ref "C27") (pin "1") (pinfunction "1_1") (pintype "passive"))
      (node (ref "C29") (pin "1") (pinfunction "1_1") (pintype "passive"))
      (node (ref "C3") (pin "1") (pinfunction "1_1") (pintype "passive"))
      (node (ref "C6") (pin "1") (pinfunction "1_1") (pintype "passive"))
      (node (ref "D1") (pin "K") (pinfunction "K_K") (pintype "passive"))
      (node (ref "D10") (pin "K") (pinfunction "K_K") (pintype "passive"))
      (node (ref "D13") (pin "K") (pinfunction "K_K") (pintype "passive"))
      (node (ref "D3") (pin "K") (pinfunction "K_K") (pintype "passive"))
      (node (ref "D5") (pin "K") (pinfunction "K_K") (pintype "passive"))
      (node (ref "IC4") (pin "3") (pinfunction "VM_3") (pintype "bidirectional"))
      (node (ref "IC4") (pin "4") (pinfunction "VDRAIN_4") (pintype "bidirectional"))
      (node (ref "Q1") (pin "MB") (pinfunction "D_MB") (pintype "passive"))
      (node (ref "Q3") (pin "MB") (pinfunction "D_MB") (pintype "passive"))
      (node (ref "Q5") (pin "MB") (pinfunction "D_MB") (pintype "passive"))
      (node (ref "R20") (pin "2") (pinfunction "2_2") (pintype "passive"))
    )
    (net (code "68") (name "VBAT") (class "Default")
      (node (ref "C5") (pin "2") (pinfunction "2_2") (pintype "passive"))
      (node (ref "R20") (pin "1") (pinfunction "1_1") (pintype "passive"))
      (node (ref "R22") (pin "2") (pinfunction "2_2") (pintype "passive"))
      (node (ref "U1") (pin "15") (pinfunction "PIO0_10/ADC1_2_15") (pintype "passive"))
    )
    (net (code "69") (name "VBAT{slash}2") (class "Default")
      (node (ref "CN5") (pin "P") (pinfunction "P_P") (pintype "passive"))
      (node (ref "F1") (pin "2") (pinfunction "2_2") (pintype "passive"))
      (node (ref "IC6") (pin "3") (pinfunction "VIN_3") (pintype "passive"))
      (node (ref "R1") (pin "2") (pinfunction "2_2") (pintype "passive"))
      (node (ref "R8") (pin "1") (pinfunction "1_1") (pintype "passive"))
    )
    (net (code "70") (name "VREF") (class "Default")
      (node (ref "R21") (pin "1") (pinfunction "1_1") (pintype "passive"))
      (node (ref "U1") (pin "10") (pinfunction "VREFP_ADC_10") (pintype "passive"))
      (node (ref "U1") (pin "14") (pinfunction "VREFP_DAC_VDDCMP_14") (pintype "passive"))
      (node (ref "U4") (pin "1") (pinfunction "K_1") (pintype "passive"))
    )
    (net (code "71") (name "unconnected-(IC3-ID-Pad5)") (class "Default")
      (node (ref "IC3") (pin "5") (pinfunction "ID_5") (pintype "passive"))
    )
    (net (code "72") (name "unconnected-(IC5-PUSH-Pad3)") (class "Default")
      (node (ref "IC5") (pin "3") (pinfunction "PUSH_3") (pintype "bidirectional"))
    )
    (net (code "73") (name "unconnected-(IC6-NC(1)-Pad7)") (class "Default")
      (node (ref "IC6") (pin "7") (pinfunction "NC(1)_7") (pintype "passive"))
    )
    (net (code "74") (name "unconnected-(IC6-NC(2)-Pad14)") (class "Default")
      (node (ref "IC6") (pin "14") (pinfunction "NC(2)_14") (pintype "passive"))
    )
    (net (code "75") (name "unconnected-(J1B-ID-PadP$4)") (class "Default")
      (node (ref "J1") (pin "P$4") (pinfunction "ID_P$4") (pintype "passive"))
    )
    (net (code "76") (name "unconnected-(U1-PIO0_13{slash}ADC1_6-Pad21)") (class "Default")
      (node (ref "U1") (pin "21") (pinfunction "PIO0_13/ADC1_6_21") (pintype "passive"))
    )
    (net (code "77") (name "unconnected-(U1-PIO0_24{slash}SCTO_OUT6-Pad43)") (class "Default")
      (node (ref "U1") (pin "43") (pinfunction "PIO0_24/SCTO_OUT6_43") (pintype "passive"))
    )
    (net (code "78") (name "unconnected-(U1-RTCXOUT-Pad32)") (class "Default")
      (node (ref "U1") (pin "32") (pinfunction "RTCXOUT_32") (pintype "passive"))
    )
    (net (code "79") (name "unconnected-(U1-SWDIO{slash}PIO0_20{slash}SCT1_OUT6{slash}TMS-Pad33)") (class "Default")
      (node (ref "U1") (pin "33") (pinfunction "SWDIO/PIO0_20/SCT1_OUT6/TMS_33") (pintype "passive"))
    )
    (net (code "80") (name "~{BRAKE}") (class "Default")
      (node (ref "IC4") (pin "30") (pinfunction "INLC_30") (pintype "bidirectional"))
      (node (ref "U1") (pin "46") (pinfunction "PIO0_27/ACMP_I1_46") (pintype "passive"))
    )
    (net (code "81") (name "~{CS}") (class "Default")
      (node (ref "IC4") (pin "21") (pinfunction "NSCS_21") (pintype "bidirectional"))
      (node (ref "U1") (pin "7") (pinfunction "PIO0_6/ADC0_2/SCT2_OUT3_7") (pintype "passive"))
    )
    (net (code "82") (name "~{FAULT}") (class "Default")
      (node (ref "IC4") (pin "17") (pinfunction "NFAULT_17") (pintype "bidirectional"))
      (node (ref "U1") (pin "13") (pinfunction "PIO0_18/SCT0_OUT5_13") (pintype "passive"))
    )
    (net (code "83") (name "~{ISP}") (class "Default")
      (node (ref "R7") (pin "1") (pinfunction "1_1") (pintype "passive"))
      (node (ref "SW2") (pin "A1") (pinfunction "A1_A1") (pintype "passive"))
      (node (ref "SW2") (pin "A2") (pinfunction "A2_A2") (pintype "passive"))
      (node (ref "U1") (pin "5") (pinfunction "PIO0_4/ADC0_4_5") (pintype "passive"))
    )
    (net (code "84") (name "~{RST}") (class "Default")
      (node (ref "D12") (pin "K") (pinfunction "K_K") (pintype "passive"))
      (node (ref "R23") (pin "1") (pinfunction "1_1") (pintype "passive"))
      (node (ref "SW1") (pin "A1") (pinfunction "A1_A1") (pintype "passive"))
      (node (ref "SW1") (pin "A2") (pinfunction "A2_A2") (pintype "passive"))
      (node (ref "U1") (pin "34") (pinfunction "RESET/PIO0_21_34") (pintype "passive"))
    )
    (net (code "85") (name "~{USB_ACK}") (class "Default")
      (node (ref "IC3") (pin "4") (pinfunction "~{ACK}_4") (pintype "passive"))
      (node (ref "R12") (pin "1") (pinfunction "1_1") (pintype "passive"))
      (node (ref "U1") (pin "22") (pinfunction "PIO0_14/ADC1_7/SCT1_OUT5_22") (pintype "passive"))
    )
  )
)
